# rapidshark-three-quarters-h-bridge-mk-1_.net
KiCad netlist of a schematic drawn in EAGLE
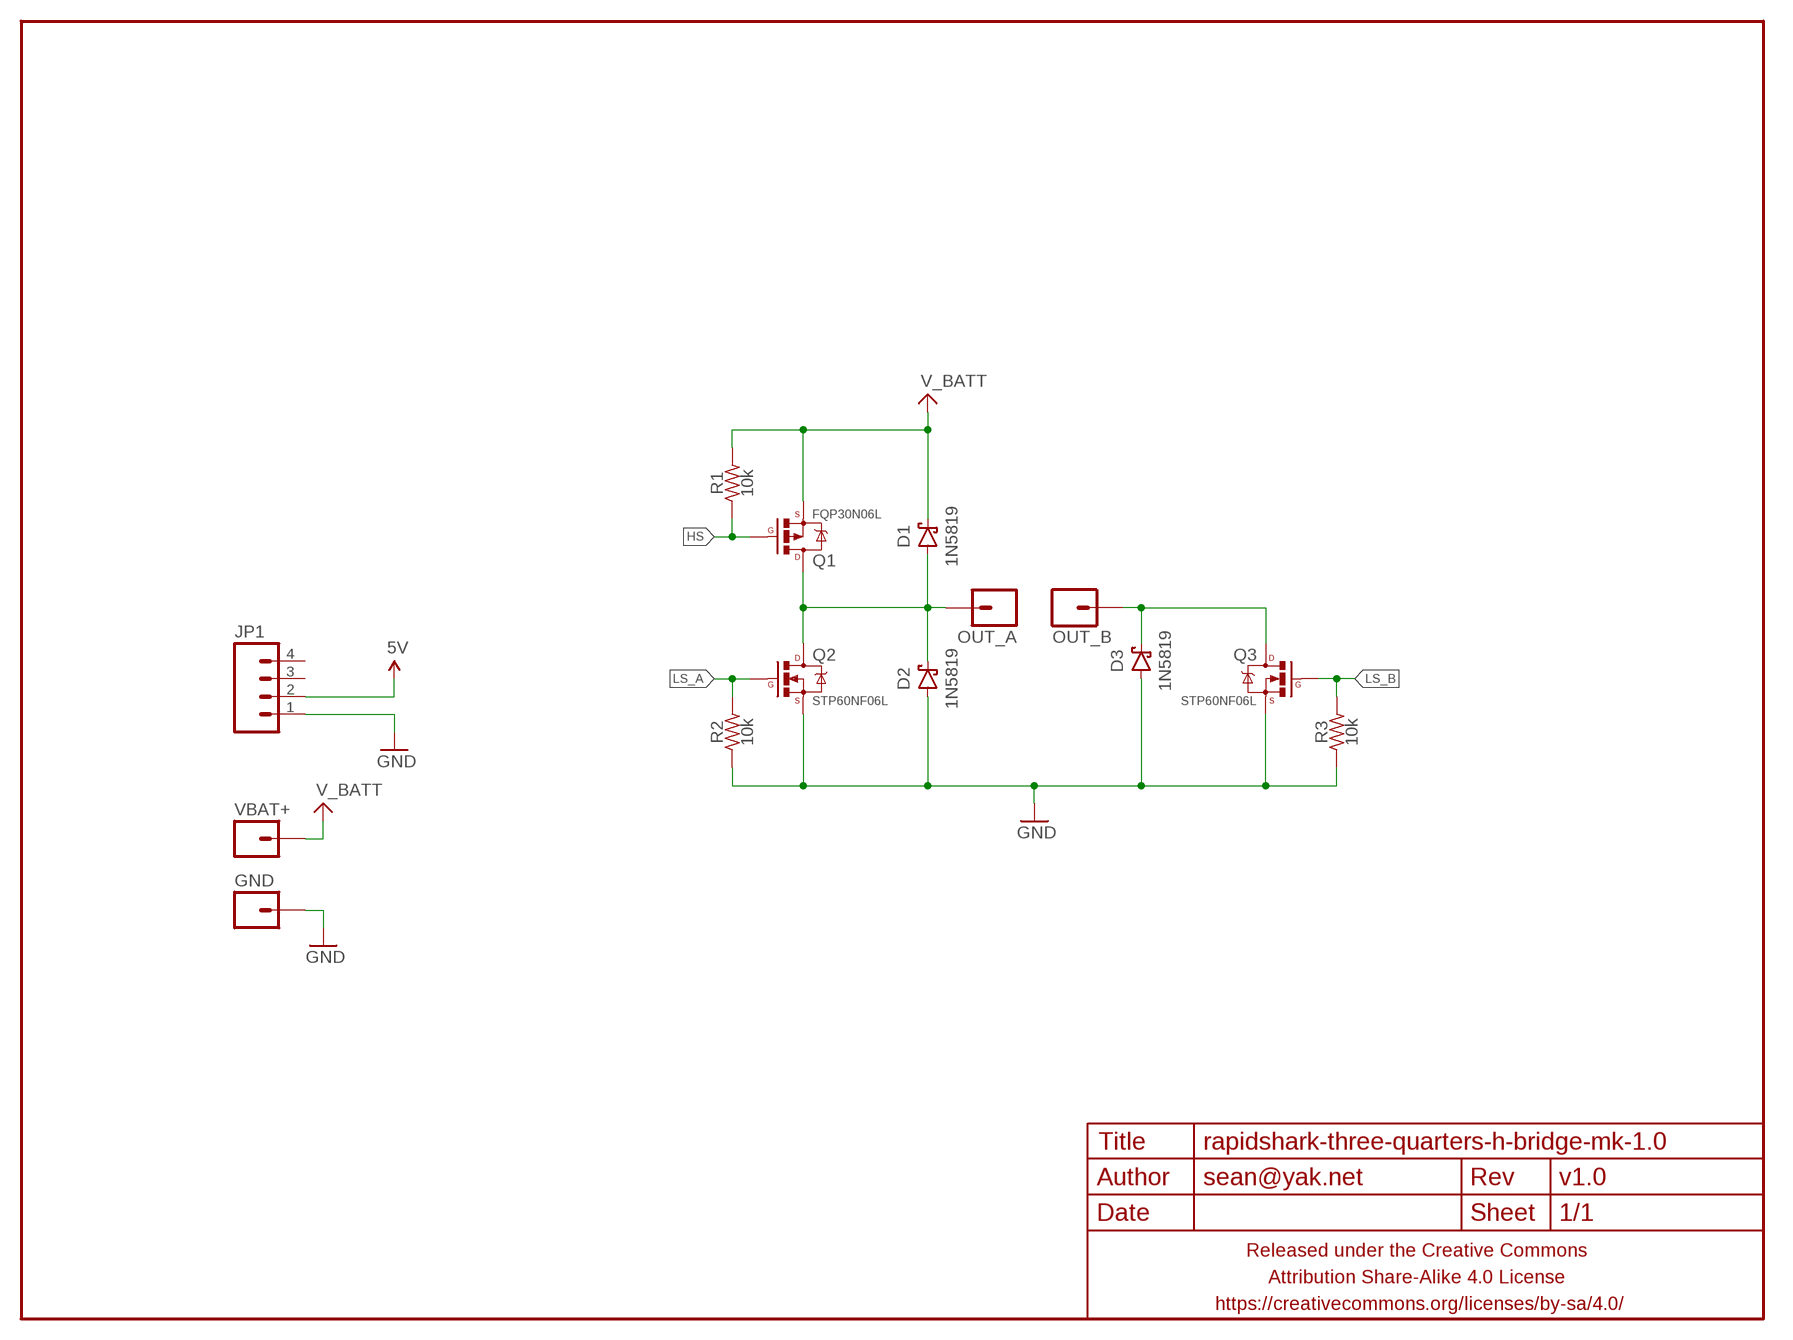
[diagram p0: schematic, sheet 1]

(export (version "E")
  (design (tool "Eeschema 10.0.6"))
  (components
    (comp (ref "D1")
      (value "1N5819")
      (footprint "eagle-import:DIODE-SCHOTTKY-10.16MM")
      (libsource (lib "eagle-import") (part "DIODE-SCHOTTKYPTH-10.16MM"))
    )
    (comp (ref "D2")
      (value "1N5819")
      (footprint "eagle-import:DIODE-SCHOTTKY-10.16MM")
      (libsource (lib "eagle-import") (part "DIODE-SCHOTTKYPTH-10.16MM"))
    )
    (comp (ref "D3")
      (value "1N5819")
      (footprint "eagle-import:DIODE-SCHOTTKY-10.16MM")
      (libsource (lib "eagle-import") (part "DIODE-SCHOTTKYPTH-10.16MM"))
    )
    (comp (ref "FRAME1")
      (value "FRAME-LETTERNO_PACKAGE")
      (footprint "eagle-import:DUMMY")
      (fields (field (name "DESIGNER") "sean@yak.net") (field (name "VERSION") "v1.0"))
      (libsource (lib "eagle-import") (part "FRAME-LETTERNO_PACKAGE"))
    )
    (comp (ref "GND")
      (value "M0112AWG")
      (footprint "eagle-import:1X01-12AWG")
      (libsource (lib "eagle-import") (part "M0112AWG"))
    )
    (comp (ref "JP1")
      (value "M04PTH")
      (footprint "eagle-import:1X04-PTH-VERT")
      (libsource (lib "eagle-import") (part "M04PTH"))
    )
    (comp (ref "OUT_A")
      (value "M0112AWG")
      (footprint "eagle-import:1X01-12AWG")
      (libsource (lib "eagle-import") (part "M0112AWG"))
    )
    (comp (ref "OUT_B")
      (value "M0112AWG")
      (footprint "eagle-import:1X01-12AWG")
      (libsource (lib "eagle-import") (part "M0112AWG"))
    )
    (comp (ref "Q1")
      (value "FQP30N06L")
      (footprint "eagle-import:TO220-THERMPAD")
      (libsource (lib "eagle-import") (part "MOSFET-PCHANNELTO-220-THERMPAD"))
    )
    (comp (ref "Q2")
      (value "STP60NF06L")
      (footprint "eagle-import:TO220-THERMPAD")
      (libsource (lib "eagle-import") (part "MOSFET-NCHANNELTO-220"))
    )
    (comp (ref "Q3")
      (value "STP60NF06L")
      (footprint "eagle-import:TO220-THERMPAD")
      (libsource (lib "eagle-import") (part "MOSFET-NCHANNELTO-220"))
    )
    (comp (ref "R1")
      (value "10k")
      (footprint "eagle-import:RESISTOR-AXIAL-PTH-5.08MM")
      (libsource (lib "eagle-import") (part "RESISTORPTH-AXIAL-5.08MM"))
    )
    (comp (ref "R2")
      (value "10k")
      (footprint "eagle-import:RESISTOR-AXIAL-PTH-5.08MM")
      (libsource (lib "eagle-import") (part "RESISTORPTH-AXIAL-5.08MM"))
    )
    (comp (ref "R3")
      (value "10k")
      (footprint "eagle-import:RESISTOR-AXIAL-PTH-5.08MM")
      (libsource (lib "eagle-import") (part "RESISTORPTH-AXIAL-5.08MM"))
    )
    (comp (ref "VBAT+")
      (value "M0112AWG")
      (footprint "eagle-import:1X01-12AWG")
      (libsource (lib "eagle-import") (part "M0112AWG"))
    )
  )
  (nets
    (net (code "1") (name "5V") (class "Default")
      (node (ref "JP1") (pin "2") (pinfunction "2_2") (pintype "passive"))
    )
    (net (code "2") (name "GND") (class "Default")
      (node (ref "D2") (pin "A") (pinfunction "A_A") (pintype "passive"))
      (node (ref "D3") (pin "A") (pinfunction "A_A") (pintype "passive"))
      (node (ref "GND") (pin "1") (pinfunction "1_1") (pintype "passive"))
      (node (ref "JP1") (pin "1") (pinfunction "1_1") (pintype "passive"))
      (node (ref "Q2") (pin "3") (pinfunction "S_3") (pintype "passive"))
      (node (ref "Q3") (pin "3") (pinfunction "S_3") (pintype "passive"))
      (node (ref "R2") (pin "P$1") (pinfunction "1_P$1") (pintype "passive"))
      (node (ref "R3") (pin "P$1") (pinfunction "1_P$1") (pintype "passive"))
    )
    (net (code "3") (name "HS") (class "Default")
      (node (ref "Q1") (pin "1") (pinfunction "G_1") (pintype "passive"))
      (node (ref "R1") (pin "P$1") (pinfunction "1_P$1") (pintype "passive"))
    )
    (net (code "4") (name "LS_A") (class "Default")
      (node (ref "Q2") (pin "1") (pinfunction "G_1") (pintype "passive"))
      (node (ref "R2") (pin "P$2") (pinfunction "2_P$2") (pintype "passive"))
    )
    (net (code "5") (name "LS_B") (class "Default")
      (node (ref "Q3") (pin "1") (pinfunction "G_1") (pintype "passive"))
      (node (ref "R3") (pin "P$2") (pinfunction "2_P$2") (pintype "passive"))
    )
    (net (code "6") (name "Net-(D1-PadA)") (class "Default")
      (node (ref "D1") (pin "A") (pinfunction "A_A") (pintype "passive"))
      (node (ref "D2") (pin "C") (pinfunction "C_C") (pintype "passive"))
      (node (ref "OUT_A") (pin "1") (pinfunction "1_1") (pintype "passive"))
      (node (ref "Q1") (pin "2@1") (pinfunction "D_2@1") (pintype "passive"))
      (node (ref "Q1") (pin "2@2") (pinfunction "D_2@2") (pintype "passive"))
      (node (ref "Q2") (pin "2@1") (pinfunction "D_2@1") (pintype "passive"))
      (node (ref "Q2") (pin "2@2") (pinfunction "D_2@2") (pintype "passive"))
    )
    (net (code "7") (name "Net-(D3-PadC)") (class "Default")
      (node (ref "D3") (pin "C") (pinfunction "C_C") (pintype "passive"))
      (node (ref "OUT_B") (pin "1") (pinfunction "1_1") (pintype "passive"))
      (node (ref "Q3") (pin "2@1") (pinfunction "D_2@1") (pintype "passive"))
      (node (ref "Q3") (pin "2@2") (pinfunction "D_2@2") (pintype "passive"))
    )
    (net (code "8") (name "V_BATT") (class "Default")
      (node (ref "D1") (pin "C") (pinfunction "C_C") (pintype "passive"))
      (node (ref "Q1") (pin "3") (pinfunction "S_3") (pintype "passive"))
      (node (ref "R1") (pin "P$2") (pinfunction "2_P$2") (pintype "passive"))
      (node (ref "VBAT+") (pin "1") (pinfunction "1_1") (pintype "passive"))
    )
    (net (code "9") (name "unconnected-(JP1-Pad3)") (class "Default")
      (node (ref "JP1") (pin "3") (pinfunction "3_3") (pintype "passive"))
    )
    (net (code "10") (name "unconnected-(JP1-Pad4)") (class "Default")
      (node (ref "JP1") (pin "4") (pinfunction "4_4") (pintype "passive"))
    )
  )
)
